# ioshield.net
KiCad netlist of a schematic drawn in EAGLE
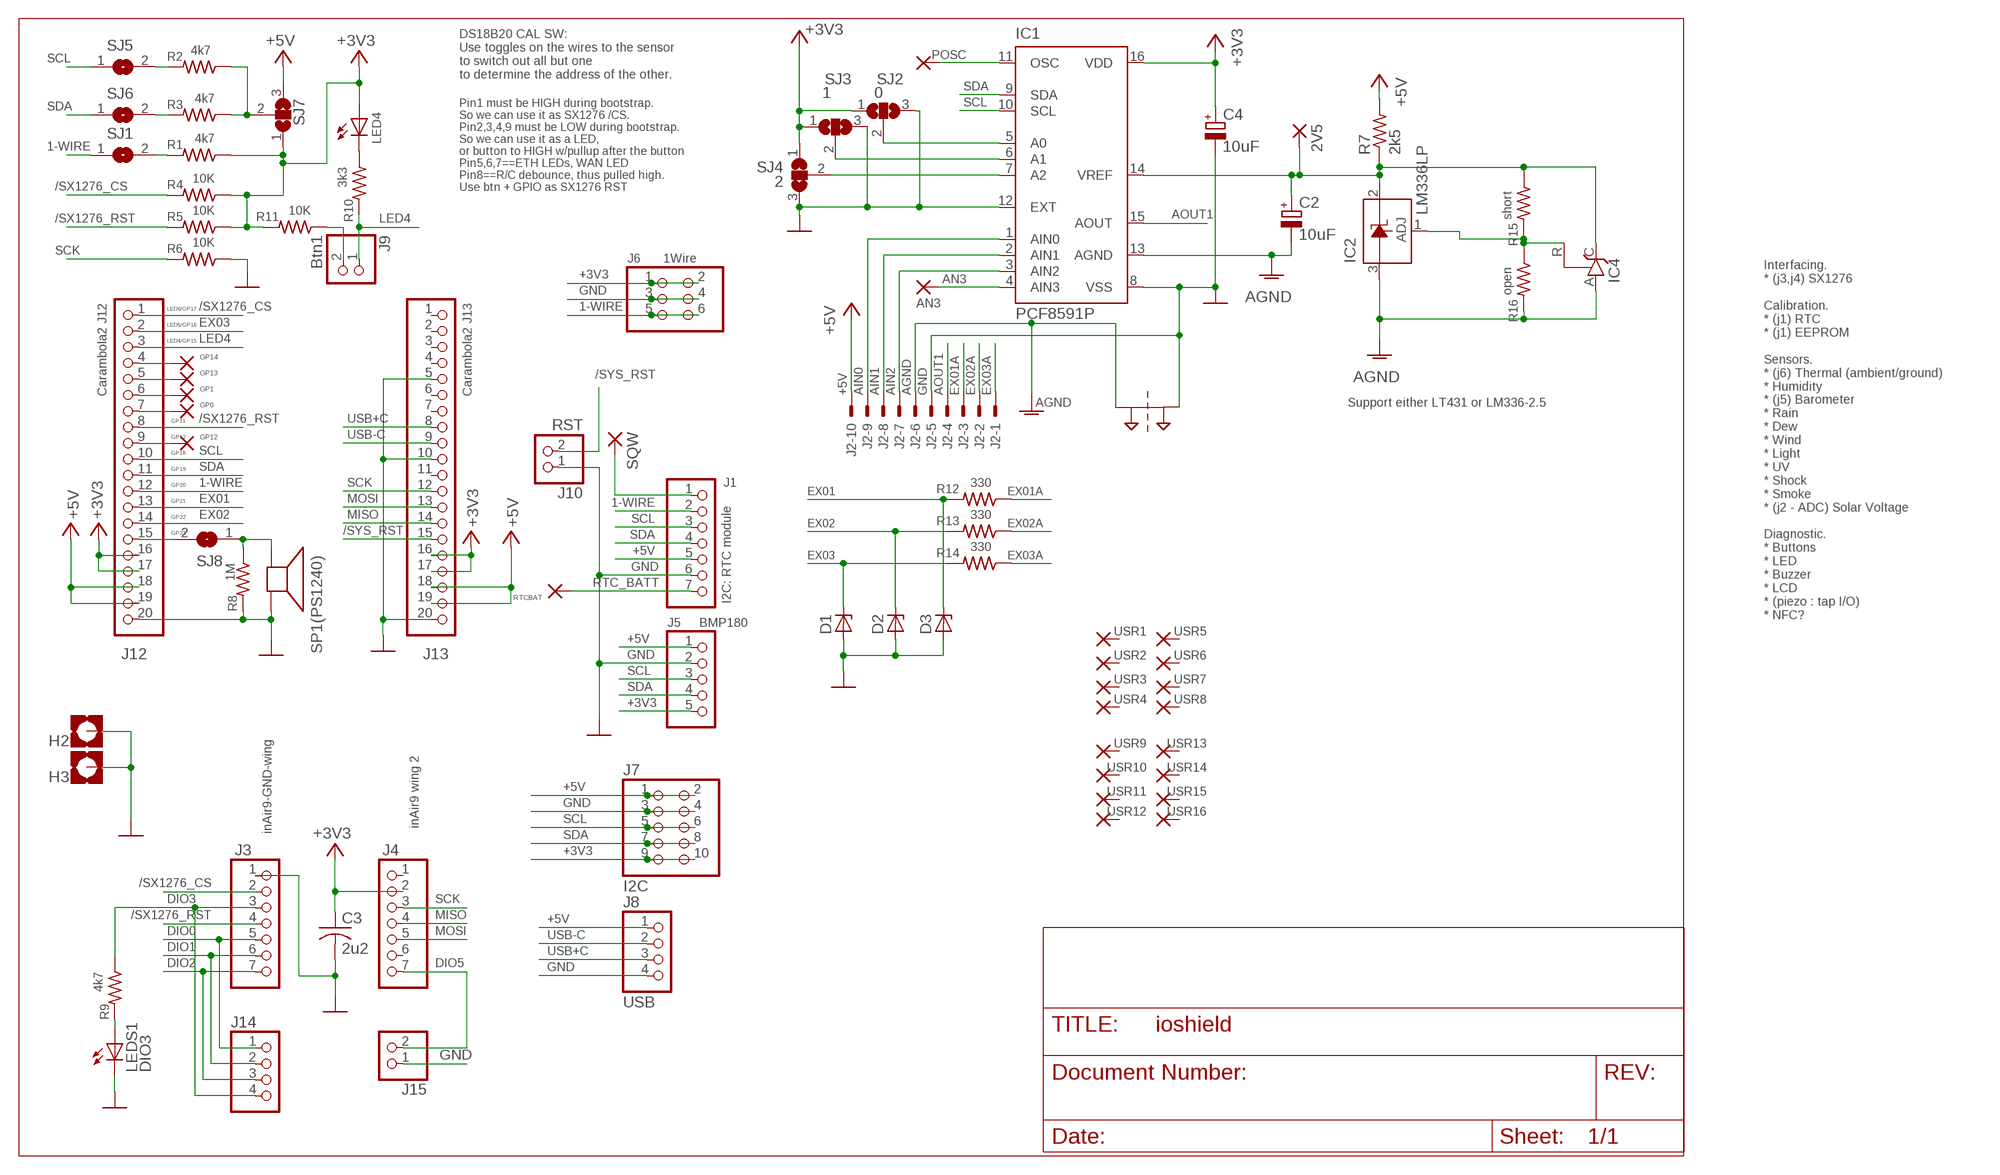
[diagram p0: schematic, sheet 1]

(export (version "E")
  (design (tool "Eeschema 10.0.6"))
  (components
    (comp (ref "2V5")
      (value "2,54/0,8")
      (footprint "eagle-import:2,54_0,8")
      (libsource (lib "eagle-import") (part "2,54/0,8"))
    )
    (comp (ref "AN3")
      (value "AN3")
      (footprint "eagle-import:2,54_0,8")
      (libsource (lib "eagle-import") (part "2,54/0,8"))
    )
    (comp (ref "C2")
      (value "10uF")
      (footprint "eagle-import:E2,5-5")
      (libsource (lib "eagle-import") (part "CPOL-EUE2.5-5"))
    )
    (comp (ref "C3")
      (value "2u2")
      (footprint "eagle-import:C1206")
      (libsource (lib "eagle-import") (part "C-USC1206"))
    )
    (comp (ref "C4")
      (value "10uF")
      (footprint "eagle-import:E2,5-5")
      (libsource (lib "eagle-import") (part "CPOL-EUE2.5-5"))
    )
    (comp (ref "D1")
      (value "ZENER-DIODEZD-2.5")
      (footprint "eagle-import:ZDIO-2.5")
      (libsource (lib "eagle-import") (part "ZENER-DIODEZD-2.5"))
    )
    (comp (ref "D2")
      (value "ZENER-DIODEZD-2.5")
      (footprint "eagle-import:ZDIO-2.5")
      (libsource (lib "eagle-import") (part "ZENER-DIODEZD-2.5"))
    )
    (comp (ref "D3")
      (value "ZENER-DIODEZD-2.5")
      (footprint "eagle-import:ZDIO-2.5")
      (libsource (lib "eagle-import") (part "ZENER-DIODEZD-2.5"))
    )
    (comp (ref "GP0")
      (value "2,54/0,8")
      (footprint "eagle-import:2,54_0,8")
      (libsource (lib "eagle-import") (part "2,54/0,8"))
    )
    (comp (ref "GP1")
      (value "2,54/0,8")
      (footprint "eagle-import:2,54_0,8")
      (libsource (lib "eagle-import") (part "2,54/0,8"))
    )
    (comp (ref "GP12")
      (value "2,54/0,8")
      (footprint "eagle-import:2,54_0,8")
      (libsource (lib "eagle-import") (part "2,54/0,8"))
    )
    (comp (ref "GP13")
      (value "2,54/0,8")
      (footprint "eagle-import:2,54_0,8")
      (libsource (lib "eagle-import") (part "2,54/0,8"))
    )
    (comp (ref "GP14")
      (value "2,54/0,8")
      (footprint "eagle-import:2,54_0,8")
      (libsource (lib "eagle-import") (part "2,54/0,8"))
    )
    (comp (ref "H2")
      (value "MOUNT-PAD-SQUARE3.2")
      (footprint "eagle-import:3,2-PAD-SQUARE")
      (libsource (lib "eagle-import") (part "MOUNT-PAD-SQUARE3.2"))
    )
    (comp (ref "H3")
      (value "MOUNT-PAD-SQUARE3.2")
      (footprint "eagle-import:3,2-PAD-SQUARE")
      (libsource (lib "eagle-import") (part "MOUNT-PAD-SQUARE3.2"))
    )
    (comp (ref "IC1")
      (value "PCF8591P")
      (footprint "eagle-import:DIL16")
      (fields (field (name "MF") "FARNELL"))
      (libsource (lib "eagle-import") (part "PCF8591P"))
    )
    (comp (ref "IC2")
      (value "LM336LP")
      (footprint "eagle-import:TO92")
      (libsource (lib "eagle-import") (part "LM336LP"))
    )
    (comp (ref "IC4")
      (value "TL431CLP")
      (footprint "eagle-import:TO92-CLP")
      (libsource (lib "eagle-import") (part "TL431CLP"))
    )
    (comp (ref "J1")
      (value "I2C: RTC module")
      (footprint "eagle-import:1X07")
      (libsource (lib "eagle-import") (part "PINHD-1X7"))
    )
    (comp (ref "J2")
      (value "22-23-2101")
      (footprint "eagle-import:22-23-2101")
      (fields (field (name "MF") "MOLEX") (field (name "MPN") "Screw Terminal"))
      (libsource (lib "eagle-import") (part "22-23-2101"))
    )
    (comp (ref "J3")
      (value "inAir9-GND-wing")
      (footprint "eagle-import:1X07")
      (libsource (lib "eagle-import") (part "PINHD-1X7"))
    )
    (comp (ref "J4")
      (value "inAir9 wing 2")
      (footprint "eagle-import:1X07")
      (libsource (lib "eagle-import") (part "PINHD-1X7"))
    )
    (comp (ref "J5")
      (value "BMP180")
      (footprint "eagle-import:1X05")
      (libsource (lib "eagle-import") (part "PINHD-1X5"))
    )
    (comp (ref "J6")
      (value "1Wire")
      (footprint "eagle-import:2X03")
      (libsource (lib "eagle-import") (part "PINHD-2X3"))
    )
    (comp (ref "J7")
      (value "I2C")
      (footprint "eagle-import:2X05")
      (libsource (lib "eagle-import") (part "PINHD-2X5"))
    )
    (comp (ref "J8")
      (value "USB")
      (footprint "eagle-import:1X04")
      (libsource (lib "eagle-import") (part "PINHD-1X4"))
    )
    (comp (ref "J9")
      (value "Btn1")
      (footprint "eagle-import:1X02")
      (libsource (lib "eagle-import") (part "PINHD-1X2"))
    )
    (comp (ref "J10")
      (value "RST")
      (footprint "eagle-import:1X02")
      (libsource (lib "eagle-import") (part "PINHD-1X2"))
    )
    (comp (ref "J12")
      (value "Carambola2 J12")
      (footprint "eagle-import:1X20")
      (libsource (lib "eagle-import") (part "PINHD-1X20"))
    )
    (comp (ref "J13")
      (value "Carambola2 J13")
      (footprint "eagle-import:1X20")
      (libsource (lib "eagle-import") (part "PINHD-1X20"))
    )
    (comp (ref "J14")
      (value "PINHD-1X4")
      (footprint "eagle-import:1X04")
      (libsource (lib "eagle-import") (part "PINHD-1X4"))
    )
    (comp (ref "J15")
      (value "PINHD-1X2")
      (footprint "eagle-import:1X02")
      (libsource (lib "eagle-import") (part "PINHD-1X2"))
    )
    (comp (ref "LED4")
      (value "LED3MM")
      (footprint "eagle-import:LED3MM")
      (libsource (lib "eagle-import") (part "LED3MM"))
    )
    (comp (ref "LEDS1")
      (value "DIO3")
      (footprint "eagle-import:LED3MM")
      (libsource (lib "eagle-import") (part "LED3MM"))
    )
    (comp (ref "POSC")
      (value "2,54/0,8")
      (footprint "eagle-import:2,54_0,8")
      (libsource (lib "eagle-import") (part "2,54/0,8"))
    )
    (comp (ref "PT1")
      (value "2PT_GND_TIE")
      (footprint "eagle-import:2PT_GND_TIE")
      (libsource (lib "eagle-import") (part "2PT_GND_TIE"))
    )
    (comp (ref "R1")
      (value "4k7")
      (footprint "eagle-import:M1206")
      (libsource (lib "eagle-import") (part "R-US_M1206"))
    )
    (comp (ref "R2")
      (value "4k7")
      (footprint "eagle-import:M1206")
      (libsource (lib "eagle-import") (part "R-US_M1206"))
    )
    (comp (ref "R3")
      (value "4k7")
      (footprint "eagle-import:M1206")
      (libsource (lib "eagle-import") (part "R-US_M1206"))
    )
    (comp (ref "R4")
      (value "10K")
      (footprint "eagle-import:M1206")
      (libsource (lib "eagle-import") (part "R-US_M1206"))
    )
    (comp (ref "R5")
      (value "10K")
      (footprint "eagle-import:M1206")
      (libsource (lib "eagle-import") (part "R-US_M1206"))
    )
    (comp (ref "R6")
      (value "10K")
      (footprint "eagle-import:M1206")
      (libsource (lib "eagle-import") (part "R-US_M1206"))
    )
    (comp (ref "R7")
      (value "2k5")
      (footprint "eagle-import:M1206")
      (libsource (lib "eagle-import") (part "R-US_M1206"))
    )
    (comp (ref "R8")
      (value "1M")
      (footprint "eagle-import:M1206")
      (libsource (lib "eagle-import") (part "R-US_M1206"))
    )
    (comp (ref "R9")
      (value "4k7")
      (footprint "eagle-import:M1206")
      (libsource (lib "eagle-import") (part "R-US_M1206"))
    )
    (comp (ref "R10")
      (value "3k3")
      (footprint "eagle-import:M1206")
      (libsource (lib "eagle-import") (part "R-US_M1206"))
    )
    (comp (ref "R11")
      (value "10K")
      (footprint "eagle-import:M1206")
      (libsource (lib "eagle-import") (part "R-US_M1206"))
    )
    (comp (ref "R12")
      (value "330")
      (footprint "eagle-import:M1206")
      (libsource (lib "eagle-import") (part "R-US_M1206"))
    )
    (comp (ref "R13")
      (value "330")
      (footprint "eagle-import:M1206")
      (libsource (lib "eagle-import") (part "R-US_M1206"))
    )
    (comp (ref "R14")
      (value "330")
      (footprint "eagle-import:M1206")
      (libsource (lib "eagle-import") (part "R-US_M1206"))
    )
    (comp (ref "R15")
      (value "short")
      (footprint "eagle-import:M1206")
      (libsource (lib "eagle-import") (part "R-US_M1206"))
    )
    (comp (ref "R16")
      (value "open")
      (footprint "eagle-import:M1206")
      (libsource (lib "eagle-import") (part "R-US_M1206"))
    )
    (comp (ref "RTCBAT")
      (value "2,54/0,8")
      (footprint "eagle-import:2,54_0,8")
      (libsource (lib "eagle-import") (part "2,54/0,8"))
    )
    (comp (ref "SJ1") (value "SJ") (footprint "eagle-import:SJ") (libsource (lib "eagle-import") (part "SJ")))
    (comp (ref "SJ2")
      (value "0")
      (footprint "eagle-import:SJ_2")
      (libsource (lib "eagle-import") (part "SJ2W"))
    )
    (comp (ref "SJ3")
      (value "1")
      (footprint "eagle-import:SJ_2")
      (libsource (lib "eagle-import") (part "SJ2W"))
    )
    (comp (ref "SJ4")
      (value "2")
      (footprint "eagle-import:SJ_2")
      (libsource (lib "eagle-import") (part "SJ2W"))
    )
    (comp (ref "SJ5") (value "SJ") (footprint "eagle-import:SJ") (libsource (lib "eagle-import") (part "SJ")))
    (comp (ref "SJ6") (value "SJ") (footprint "eagle-import:SJ") (libsource (lib "eagle-import") (part "SJ")))
    (comp (ref "SJ7")
      (value "SJ2W")
      (footprint "eagle-import:SJ_2")
      (libsource (lib "eagle-import") (part "SJ2W"))
    )
    (comp (ref "SJ8") (value "SJ") (footprint "eagle-import:SJ") (libsource (lib "eagle-import") (part "SJ")))
    (comp (ref "SP1(PS1240)")
      (value "SPEAKER/AL11P")
      (footprint "eagle-import:AL11P")
      (libsource (lib "eagle-import") (part "SPEAKER/AL11P"))
    )
    (comp (ref "SQW")
      (value "2,54/0,8")
      (footprint "eagle-import:2,54_0,8")
      (libsource (lib "eagle-import") (part "2,54/0,8"))
    )
    (comp (ref "USR1")
      (value "1,6/0,8")
      (footprint "eagle-import:1,6_0,8")
      (libsource (lib "eagle-import") (part "1,6/0,8"))
    )
    (comp (ref "USR2")
      (value "1,6/0,8")
      (footprint "eagle-import:1,6_0,8")
      (libsource (lib "eagle-import") (part "1,6/0,8"))
    )
    (comp (ref "USR3")
      (value "1,6/0,8")
      (footprint "eagle-import:1,6_0,8")
      (libsource (lib "eagle-import") (part "1,6/0,8"))
    )
    (comp (ref "USR4")
      (value "1,6/0,8")
      (footprint "eagle-import:1,6_0,8")
      (libsource (lib "eagle-import") (part "1,6/0,8"))
    )
    (comp (ref "USR5")
      (value "1,6/0,8")
      (footprint "eagle-import:1,6_0,8")
      (libsource (lib "eagle-import") (part "1,6/0,8"))
    )
    (comp (ref "USR6")
      (value "1,6/0,8")
      (footprint "eagle-import:1,6_0,8")
      (libsource (lib "eagle-import") (part "1,6/0,8"))
    )
    (comp (ref "USR7")
      (value "1,6/0,8")
      (footprint "eagle-import:1,6_0,8")
      (libsource (lib "eagle-import") (part "1,6/0,8"))
    )
    (comp (ref "USR8")
      (value "1,6/0,8")
      (footprint "eagle-import:1,6_0,8")
      (libsource (lib "eagle-import") (part "1,6/0,8"))
    )
    (comp (ref "USR9")
      (value "1,6/0,8")
      (footprint "eagle-import:1,6_0,8")
      (libsource (lib "eagle-import") (part "1,6/0,8"))
    )
    (comp (ref "USR10")
      (value "1,6/0,8")
      (footprint "eagle-import:1,6_0,8")
      (libsource (lib "eagle-import") (part "1,6/0,8"))
    )
    (comp (ref "USR11")
      (value "1,6/0,8")
      (footprint "eagle-import:1,6_0,8")
      (libsource (lib "eagle-import") (part "1,6/0,8"))
    )
    (comp (ref "USR12")
      (value "1,6/0,8")
      (footprint "eagle-import:1,6_0,8")
      (libsource (lib "eagle-import") (part "1,6/0,8"))
    )
    (comp (ref "USR13")
      (value "1,6/0,8")
      (footprint "eagle-import:1,6_0,8")
      (libsource (lib "eagle-import") (part "1,6/0,8"))
    )
    (comp (ref "USR14")
      (value "1,6/0,8")
      (footprint "eagle-import:1,6_0,8")
      (libsource (lib "eagle-import") (part "1,6/0,8"))
    )
    (comp (ref "USR15")
      (value "1,6/0,8")
      (footprint "eagle-import:1,6_0,8")
      (libsource (lib "eagle-import") (part "1,6/0,8"))
    )
    (comp (ref "USR16")
      (value "1,6/0,8")
      (footprint "eagle-import:1,6_0,8")
      (libsource (lib "eagle-import") (part "1,6/0,8"))
    )
  )
  (nets
    (net (code "1") (name "+3V3") (class "Default")
      (node (ref "C3") (pin "1") (pinfunction "1_1") (pintype "passive"))
      (node (ref "C4") (pin "+") (pinfunction "+_+") (pintype "passive"))
      (node (ref "IC1") (pin "16") (pinfunction "VDD_16") (pintype "power_in"))
      (node (ref "J12") (pin "16") (pinfunction "16_16") (pintype "passive"))
      (node (ref "J12") (pin "17") (pinfunction "17_17") (pintype "passive"))
      (node (ref "J13") (pin "16") (pinfunction "16_16") (pintype "passive"))
      (node (ref "J13") (pin "17") (pinfunction "17_17") (pintype "passive"))
      (node (ref "J4") (pin "2") (pinfunction "2_2") (pintype "passive"))
      (node (ref "J5") (pin "5") (pinfunction "5_5") (pintype "passive"))
      (node (ref "J6") (pin "1") (pinfunction "1_1") (pintype "passive"))
      (node (ref "J6") (pin "2") (pinfunction "2_2") (pintype "passive"))
      (node (ref "J7") (pin "10") (pinfunction "10_10") (pintype "passive"))
      (node (ref "J7") (pin "9") (pinfunction "9_9") (pintype "passive"))
      (node (ref "LED4") (pin "A") (pinfunction "A_A") (pintype "passive"))
      (node (ref "R1") (pin "1") (pinfunction "1_1") (pintype "passive"))
      (node (ref "R11") (pin "2") (pinfunction "2_2") (pintype "passive"))
      (node (ref "R4") (pin "1") (pinfunction "1_1") (pintype "passive"))
      (node (ref "R5") (pin "1") (pinfunction "1_1") (pintype "passive"))
      (node (ref "SJ2") (pin "1") (pinfunction "1_1") (pintype "passive"))
      (node (ref "SJ3") (pin "1") (pinfunction "1_1") (pintype "passive"))
      (node (ref "SJ4") (pin "1") (pinfunction "1_1") (pintype "passive"))
      (node (ref "SJ7") (pin "1") (pinfunction "1_1") (pintype "passive"))
    )
    (net (code "2") (name "+5V") (class "Default")
      (node (ref "J1") (pin "5") (pinfunction "5_5") (pintype "passive"))
      (node (ref "J12") (pin "18") (pinfunction "18_18") (pintype "passive"))
      (node (ref "J12") (pin "19") (pinfunction "19_19") (pintype "passive"))
      (node (ref "J13") (pin "18") (pinfunction "18_18") (pintype "passive"))
      (node (ref "J13") (pin "19") (pinfunction "19_19") (pintype "passive"))
      (node (ref "J2") (pin "10") (pinfunction "S_10") (pintype "passive"))
      (node (ref "J5") (pin "1") (pinfunction "1_1") (pintype "passive"))
      (node (ref "J7") (pin "1") (pinfunction "1_1") (pintype "passive"))
      (node (ref "J7") (pin "2") (pinfunction "2_2") (pintype "passive"))
      (node (ref "J8") (pin "1") (pinfunction "1_1") (pintype "passive"))
      (node (ref "R7") (pin "2") (pinfunction "2_2") (pintype "passive"))
      (node (ref "SJ7") (pin "3") (pinfunction "3_3") (pintype "passive"))
    )
    (net (code "3") (name "/1-WIRE") (class "Default")
      (node (ref "J1") (pin "2") (pinfunction "2_2") (pintype "passive"))
      (node (ref "J12") (pin "12") (pinfunction "12_12") (pintype "passive"))
      (node (ref "J6") (pin "5") (pinfunction "5_5") (pintype "passive"))
      (node (ref "J6") (pin "6") (pinfunction "6_6") (pintype "passive"))
      (node (ref "SJ1") (pin "1") (pinfunction "1_1") (pintype "passive"))
    )
    (net (code "4") (name "/AIN0") (class "Default")
      (node (ref "IC1") (pin "1") (pinfunction "AIN0_1") (pintype "input"))
      (node (ref "J2") (pin "9") (pinfunction "S_9") (pintype "passive"))
    )
    (net (code "5") (name "/AIN1") (class "Default")
      (node (ref "IC1") (pin "2") (pinfunction "AIN1_2") (pintype "input"))
      (node (ref "J2") (pin "8") (pinfunction "S_8") (pintype "passive"))
    )
    (net (code "6") (name "/AIN2") (class "Default")
      (node (ref "IC1") (pin "3") (pinfunction "AIN2_3") (pintype "input"))
      (node (ref "J2") (pin "7") (pinfunction "S_7") (pintype "passive"))
    )
    (net (code "7") (name "/AOUT1") (class "Default")
      (node (ref "IC1") (pin "15") (pinfunction "AOUT_15") (pintype "output"))
      (node (ref "J2") (pin "4") (pinfunction "S_4") (pintype "passive"))
    )
    (net (code "8") (name "/DIO0") (class "Default")
      (node (ref "J14") (pin "1") (pinfunction "1_1") (pintype "passive"))
      (node (ref "J3") (pin "5") (pinfunction "5_5") (pintype "passive"))
    )
    (net (code "9") (name "/DIO1") (class "Default")
      (node (ref "J14") (pin "2") (pinfunction "2_2") (pintype "passive"))
      (node (ref "J3") (pin "6") (pinfunction "6_6") (pintype "passive"))
    )
    (net (code "10") (name "/DIO2") (class "Default")
      (node (ref "J14") (pin "3") (pinfunction "3_3") (pintype "passive"))
      (node (ref "J3") (pin "7") (pinfunction "7_7") (pintype "passive"))
    )
    (net (code "11") (name "/DIO3") (class "Default")
      (node (ref "J14") (pin "4") (pinfunction "4_4") (pintype "passive"))
      (node (ref "J3") (pin "3") (pinfunction "3_3") (pintype "passive"))
      (node (ref "R9") (pin "1") (pinfunction "1_1") (pintype "passive"))
    )
    (net (code "12") (name "/DIO5") (class "Default")
      (node (ref "J15") (pin "2") (pinfunction "2_2") (pintype "passive"))
      (node (ref "J4") (pin "7") (pinfunction "7_7") (pintype "passive"))
    )
    (net (code "13") (name "/EX01") (class "Default")
      (node (ref "D3") (pin "C") (pinfunction "C_C") (pintype "passive"))
      (node (ref "J12") (pin "13") (pinfunction "13_13") (pintype "passive"))
      (node (ref "R12") (pin "2") (pinfunction "2_2") (pintype "passive"))
    )
    (net (code "14") (name "/EX01A") (class "Default")
      (node (ref "J2") (pin "3") (pinfunction "S_3") (pintype "passive"))
      (node (ref "R12") (pin "1") (pinfunction "1_1") (pintype "passive"))
    )
    (net (code "15") (name "/EX02") (class "Default")
      (node (ref "D2") (pin "C") (pinfunction "C_C") (pintype "passive"))
      (node (ref "J12") (pin "14") (pinfunction "14_14") (pintype "passive"))
      (node (ref "R13") (pin "2") (pinfunction "2_2") (pintype "passive"))
    )
    (net (code "16") (name "/EX02A") (class "Default")
      (node (ref "J2") (pin "2") (pinfunction "S_2") (pintype "passive"))
      (node (ref "R13") (pin "1") (pinfunction "1_1") (pintype "passive"))
    )
    (net (code "17") (name "/EX03") (class "Default")
      (node (ref "D1") (pin "C") (pinfunction "C_C") (pintype "passive"))
      (node (ref "J12") (pin "2") (pinfunction "2_2") (pintype "passive"))
      (node (ref "R14") (pin "2") (pinfunction "2_2") (pintype "passive"))
    )
    (net (code "18") (name "/EX03A") (class "Default")
      (node (ref "J2") (pin "1") (pinfunction "S_1") (pintype "passive"))
      (node (ref "R14") (pin "1") (pinfunction "1_1") (pintype "passive"))
    )
    (net (code "19") (name "/LED4") (class "Default")
      (node (ref "J12") (pin "3") (pinfunction "3_3") (pintype "passive"))
      (node (ref "J9") (pin "1") (pinfunction "1_1") (pintype "passive"))
      (node (ref "R10") (pin "2") (pinfunction "2_2") (pintype "passive"))
    )
    (net (code "20") (name "/MISO") (class "Default")
      (node (ref "J13") (pin "14") (pinfunction "14_14") (pintype "passive"))
      (node (ref "J4") (pin "4") (pinfunction "4_4") (pintype "passive"))
    )
    (net (code "21") (name "/MOSI") (class "Default")
      (node (ref "J13") (pin "13") (pinfunction "13_13") (pintype "passive"))
      (node (ref "J4") (pin "5") (pinfunction "5_5") (pintype "passive"))
    )
    (net (code "22") (name "/RTC_BATT") (class "Default")
      (node (ref "J1") (pin "7") (pinfunction "7_7") (pintype "passive"))
      (node (ref "RTCBAT") (pin "1") (pinfunction "P_1") (pintype "passive"))
    )
    (net (code "23") (name "/SCK") (class "Default")
      (node (ref "J13") (pin "12") (pinfunction "12_12") (pintype "passive"))
      (node (ref "J4") (pin "3") (pinfunction "3_3") (pintype "passive"))
      (node (ref "R6") (pin "2") (pinfunction "2_2") (pintype "passive"))
    )
    (net (code "24") (name "/SCL") (class "Default")
      (node (ref "IC1") (pin "10") (pinfunction "SCL_10") (pintype "input"))
      (node (ref "J1") (pin "3") (pinfunction "3_3") (pintype "passive"))
      (node (ref "J12") (pin "10") (pinfunction "10_10") (pintype "passive"))
      (node (ref "J5") (pin "3") (pinfunction "3_3") (pintype "passive"))
      (node (ref "J7") (pin "5") (pinfunction "5_5") (pintype "passive"))
      (node (ref "J7") (pin "6") (pinfunction "6_6") (pintype "passive"))
      (node (ref "SJ5") (pin "1") (pinfunction "1_1") (pintype "passive"))
    )
    (net (code "25") (name "/SDA") (class "Default")
      (node (ref "IC1") (pin "9") (pinfunction "SDA_9") (pintype "bidirectional"))
      (node (ref "J1") (pin "4") (pinfunction "4_4") (pintype "passive"))
      (node (ref "J12") (pin "11") (pinfunction "11_11") (pintype "passive"))
      (node (ref "J5") (pin "4") (pinfunction "4_4") (pintype "passive"))
      (node (ref "J7") (pin "7") (pinfunction "7_7") (pintype "passive"))
      (node (ref "J7") (pin "8") (pinfunction "8_8") (pintype "passive"))
      (node (ref "SJ6") (pin "1") (pinfunction "1_1") (pintype "passive"))
    )
    (net (code "26") (name "/USB+C") (class "Default")
      (node (ref "J13") (pin "8") (pinfunction "8_8") (pintype "passive"))
      (node (ref "J8") (pin "3") (pinfunction "3_3") (pintype "passive"))
    )
    (net (code "27") (name "/USB-C") (class "Default")
      (node (ref "J13") (pin "9") (pinfunction "9_9") (pintype "passive"))
      (node (ref "J8") (pin "2") (pinfunction "2_2") (pintype "passive"))
    )
    (net (code "28") (name "/{slash}SX1276_CS") (class "Default")
      (node (ref "J12") (pin "1") (pinfunction "1_1") (pintype "passive"))
      (node (ref "J3") (pin "2") (pinfunction "2_2") (pintype "passive"))
      (node (ref "R4") (pin "2") (pinfunction "2_2") (pintype "passive"))
    )
    (net (code "29") (name "/{slash}SX1276_RST") (class "Default")
      (node (ref "J12") (pin "8") (pinfunction "8_8") (pintype "passive"))
      (node (ref "J3") (pin "4") (pinfunction "4_4") (pintype "passive"))
      (node (ref "R5") (pin "2") (pinfunction "2_2") (pintype "passive"))
    )
    (net (code "30") (name "/{slash}SYS_RST") (class "Default")
      (node (ref "J10") (pin "2") (pinfunction "2_2") (pintype "passive"))
      (node (ref "J13") (pin "15") (pinfunction "15_15") (pintype "passive"))
    )
    (net (code "31") (name "AGND") (class "Default")
      (node (ref "C2") (pin "-") (pinfunction "-_-") (pintype "passive"))
      (node (ref "IC1") (pin "13") (pinfunction "AGND_13") (pintype "power_in"))
      (node (ref "IC2") (pin "3") (pinfunction "A_3") (pintype "input"))
      (node (ref "IC4") (pin "A") (pinfunction "A_A") (pintype "passive"))
      (node (ref "J2") (pin "6") (pinfunction "S_6") (pintype "passive"))
      (node (ref "PT1") (pin "P$1") (pinfunction "P$1_P$1") (pintype "bidirectional"))
      (node (ref "R16") (pin "2") (pinfunction "2_2") (pintype "passive"))
    )
    (net (code "32") (name "GND") (class "Default")
      (node (ref "C3") (pin "2") (pinfunction "2_2") (pintype "passive"))
      (node (ref "C4") (pin "-") (pinfunction "-_-") (pintype "passive"))
      (node (ref "D1") (pin "A") (pinfunction "A_A") (pintype "passive"))
      (node (ref "D2") (pin "A") (pinfunction "A_A") (pintype "passive"))
      (node (ref "D3") (pin "A") (pinfunction "A_A") (pintype "passive"))
      (node (ref "H2") (pin "B3,2") (pinfunction "MOUNT_B3,2") (pintype "passive"))
      (node (ref "H3") (pin "B3,2") (pinfunction "MOUNT_B3,2") (pintype "passive"))
      (node (ref "IC1") (pin "12") (pinfunction "EXT_12") (pintype "input"))
      (node (ref "IC1") (pin "8") (pinfunction "VSS_8") (pintype "power_in"))
      (node (ref "J1") (pin "6") (pinfunction "6_6") (pintype "passive"))
      (node (ref "J10") (pin "1") (pinfunction "1_1") (pintype "passive"))
      (node (ref "J12") (pin "20") (pinfunction "20_20") (pintype "passive"))
      (node (ref "J13") (pin "10") (pinfunction "10_10") (pintype "passive"))
      (node (ref "J13") (pin "20") (pinfunction "20_20") (pintype "passive"))
      (node (ref "J13") (pin "5") (pinfunction "5_5") (pintype "passive"))
      (node (ref "J15") (pin "1") (pinfunction "1_1") (pintype "passive"))
      (node (ref "J2") (pin "5") (pinfunction "S_5") (pintype "passive"))
      (node (ref "J3") (pin "1") (pinfunction "1_1") (pintype "passive"))
      (node (ref "J5") (pin "2") (pinfunction "2_2") (pintype "passive"))
      (node (ref "J6") (pin "3") (pinfunction "3_3") (pintype "passive"))
      (node (ref "J6") (pin "4") (pinfunction "4_4") (pintype "passive"))
      (node (ref "J7") (pin "3") (pinfunction "3_3") (pintype "passive"))
      (node (ref "J7") (pin "4") (pinfunction "4_4") (pintype "passive"))
      (node (ref "J8") (pin "4") (pinfunction "4_4") (pintype "passive"))
      (node (ref "LEDS1") (pin "K") (pinfunction "C_K") (pintype "passive"))
      (node (ref "PT1") (pin "P$2") (pinfunction "P$2_P$2") (pintype "bidirectional"))
      (node (ref "R6") (pin "1") (pinfunction "1_1") (pintype "passive"))
      (node (ref "R8") (pin "2") (pinfunction "2_2") (pintype "passive"))
      (node (ref "SJ2") (pin "3") (pinfunction "3_3") (pintype "passive"))
      (node (ref "SJ3") (pin "3") (pinfunction "3_3") (pintype "passive"))
      (node (ref "SJ4") (pin "3") (pinfunction "3_3") (pintype "passive"))
      (node (ref "SP1(PS1240)") (pin "-") (pinfunction "-_-") (pintype "passive"))
    )
    (net (code "33") (name "Net-(2V5-P)") (class "Default")
      (node (ref "2V5") (pin "1") (pinfunction "P_1") (pintype "passive"))
      (node (ref "C2") (pin "+") (pinfunction "+_+") (pintype "passive"))
      (node (ref "IC1") (pin "14") (pinfunction "VREF_14") (pintype "input"))
      (node (ref "IC2") (pin "2") (pinfunction "C_2") (pintype "passive"))
      (node (ref "IC4") (pin "C") (pinfunction "C_C") (pintype "passive"))
      (node (ref "R15") (pin "1") (pinfunction "1_1") (pintype "passive"))
      (node (ref "R7") (pin "1") (pinfunction "1_1") (pintype "passive"))
    )
    (net (code "34") (name "Net-(AN3-P)") (class "Default")
      (node (ref "AN3") (pin "1") (pinfunction "P_1") (pintype "passive"))
      (node (ref "IC1") (pin "4") (pinfunction "AIN3_4") (pintype "input"))
    )
    (net (code "35") (name "Net-(GP0-P)") (class "Default")
      (node (ref "GP0") (pin "1") (pinfunction "P_1") (pintype "passive"))
      (node (ref "J12") (pin "7") (pinfunction "7_7") (pintype "passive"))
    )
    (net (code "36") (name "Net-(GP1-P)") (class "Default")
      (node (ref "GP1") (pin "1") (pinfunction "P_1") (pintype "passive"))
      (node (ref "J12") (pin "6") (pinfunction "6_6") (pintype "passive"))
    )
    (net (code "37") (name "Net-(GP12-P)") (class "Default")
      (node (ref "GP12") (pin "1") (pinfunction "P_1") (pintype "passive"))
      (node (ref "J12") (pin "9") (pinfunction "9_9") (pintype "passive"))
    )
    (net (code "38") (name "Net-(GP13-P)") (class "Default")
      (node (ref "GP13") (pin "1") (pinfunction "P_1") (pintype "passive"))
      (node (ref "J12") (pin "5") (pinfunction "5_5") (pintype "passive"))
    )
    (net (code "39") (name "Net-(GP14-P)") (class "Default")
      (node (ref "GP14") (pin "1") (pinfunction "P_1") (pintype "passive"))
      (node (ref "J12") (pin "4") (pinfunction "4_4") (pintype "passive"))
    )
    (net (code "40") (name "Net-(IC1-A0)") (class "Default")
      (node (ref "IC1") (pin "5") (pinfunction "A0_5") (pintype "input"))
      (node (ref "SJ2") (pin "2") (pinfunction "2_2") (pintype "passive"))
    )
    (net (code "41") (name "Net-(IC1-A1)") (class "Default")
      (node (ref "IC1") (pin "6") (pinfunction "A1_6") (pintype "input"))
      (node (ref "SJ3") (pin "2") (pinfunction "2_2") (pintype "passive"))
    )
    (net (code "42") (name "Net-(IC1-A2)") (class "Default")
      (node (ref "IC1") (pin "7") (pinfunction "A2_7") (pintype "input"))
      (node (ref "SJ4") (pin "2") (pinfunction "2_2") (pintype "passive"))
    )
    (net (code "43") (name "Net-(IC1-OSC)") (class "Default")
      (node (ref "IC1") (pin "11") (pinfunction "OSC_11") (pintype "input"))
      (node (ref "POSC") (pin "1") (pinfunction "P_1") (pintype "passive"))
    )
    (net (code "44") (name "Net-(IC2-ADJ)") (class "Default")
      (node (ref "IC2") (pin "1") (pinfunction "ADJ_1") (pintype "input"))
      (node (ref "IC4") (pin "R") (pinfunction "R_R") (pintype "passive"))
      (node (ref "R15") (pin "2") (pinfunction "2_2") (pintype "passive"))
      (node (ref "R16") (pin "1") (pinfunction "1_1") (pintype "passive"))
    )
    (net (code "45") (name "Net-(J9-Pad2)") (class "Default")
      (node (ref "J9") (pin "2") (pinfunction "2_2") (pintype "passive"))
      (node (ref "R11") (pin "1") (pinfunction "1_1") (pintype "passive"))
    )
    (net (code "46") (name "Net-(J12-Pad15)") (class "Default")
      (node (ref "J12") (pin "15") (pinfunction "15_15") (pintype "passive"))
      (node (ref "SJ8") (pin "2") (pinfunction "2_2") (pintype "passive"))
    )
    (net (code "47") (name "Net-(LED4-C)") (class "Default")
      (node (ref "LED4") (pin "K") (pinfunction "C_K") (pintype "passive"))
      (node (ref "R10") (pin "1") (pinfunction "1_1") (pintype "passive"))
    )
    (net (code "48") (name "Net-(LEDS1-PadA)") (class "Default")
      (node (ref "LEDS1") (pin "A") (pinfunction "A_A") (pintype "passive"))
      (node (ref "R9") (pin "2") (pinfunction "2_2") (pintype "passive"))
    )
    (net (code "49") (name "Net-(R1-Pad2)") (class "Default")
      (node (ref "R1") (pin "2") (pinfunction "2_2") (pintype "passive"))
      (node (ref "SJ1") (pin "2") (pinfunction "2_2") (pintype "passive"))
    )
    (net (code "50") (name "Net-(R2-Pad1)") (class "Default")
      (node (ref "R2") (pin "1") (pinfunction "1_1") (pintype "passive"))
      (node (ref "R3") (pin "1") (pinfunction "1_1") (pintype "passive"))
      (node (ref "SJ7") (pin "2") (pinfunction "2_2") (pintype "passive"))
    )
    (net (code "51") (name "Net-(R2-Pad2)") (class "Default")
      (node (ref "R2") (pin "2") (pinfunction "2_2") (pintype "passive"))
      (node (ref "SJ5") (pin "2") (pinfunction "2_2") (pintype "passive"))
    )
    (net (code "52") (name "Net-(R3-Pad2)") (class "Default")
      (node (ref "R3") (pin "2") (pinfunction "2_2") (pintype "passive"))
      (node (ref "SJ6") (pin "2") (pinfunction "2_2") (pintype "passive"))
    )
    (net (code "53") (name "Net-(R8-Pad1)") (class "Default")
      (node (ref "R8") (pin "1") (pinfunction "1_1") (pintype "passive"))
      (node (ref "SJ8") (pin "1") (pinfunction "1_1") (pintype "passive"))
      (node (ref "SP1(PS1240)") (pin "+") (pinfunction "+_+") (pintype "passive"))
    )
    (net (code "54") (name "Net-(SQW-P)") (class "Default")
      (node (ref "J1") (pin "1") (pinfunction "1_1") (pintype "passive"))
      (node (ref "SQW") (pin "1") (pinfunction "P_1") (pintype "passive"))
    )
    (net (code "55") (name "unconnected-(J4-Pad1)") (class "Default")
      (node (ref "J4") (pin "1") (pinfunction "1_1") (pintype "passive"))
    )
    (net (code "56") (name "unconnected-(J4-Pad6)") (class "Default")
      (node (ref "J4") (pin "6") (pinfunction "6_6") (pintype "passive"))
    )
    (net (code "57") (name "unconnected-(J13-Pad1)") (class "Default")
      (node (ref "J13") (pin "1") (pinfunction "1_1") (pintype "passive"))
    )
    (net (code "58") (name "unconnected-(J13-Pad2)") (class "Default")
      (node (ref "J13") (pin "2") (pinfunction "2_2") (pintype "passive"))
    )
    (net (code "59") (name "unconnected-(J13-Pad3)") (class "Default")
      (node (ref "J13") (pin "3") (pinfunction "3_3") (pintype "passive"))
    )
    (net (code "60") (name "unconnected-(J13-Pad4)") (class "Default")
      (node (ref "J13") (pin "4") (pinfunction "4_4") (pintype "passive"))
    )
    (net (code "61") (name "unconnected-(J13-Pad6)") (class "Default")
      (node (ref "J13") (pin "6") (pinfunction "6_6") (pintype "passive"))
    )
    (net (code "62") (name "unconnected-(J13-Pad7)") (class "Default")
      (node (ref "J13") (pin "7") (pinfunction "7_7") (pintype "passive"))
    )
    (net (code "63") (name "unconnected-(J13-Pad11)") (class "Default")
      (node (ref "J13") (pin "11") (pinfunction "11_11") (pintype "passive"))
    )
    (net (code "64") (name "unconnected-(USR1-P-Pad1)") (class "Default")
      (node (ref "USR1") (pin "1") (pinfunction "P_1") (pintype "passive"))
    )
    (net (code "65") (name "unconnected-(USR2-P-Pad1)") (class "Default")
      (node (ref "USR2") (pin "1") (pinfunction "P_1") (pintype "passive"))
    )
    (net (code "66") (name "unconnected-(USR3-P-Pad1)") (class "Default")
      (node (ref "USR3") (pin "1") (pinfunction "P_1") (pintype "passive"))
    )
    (net (code "67") (name "unconnected-(USR4-P-Pad1)") (class "Default")
      (node (ref "USR4") (pin "1") (pinfunction "P_1") (pintype "passive"))
    )
    (net (code "68") (name "unconnected-(USR5-P-Pad1)") (class "Default")
      (node (ref "USR5") (pin "1") (pinfunction "P_1") (pintype "passive"))
    )
    (net (code "69") (name "unconnected-(USR6-P-Pad1)") (class "Default")
      (node (ref "USR6") (pin "1") (pinfunction "P_1") (pintype "passive"))
    )
    (net (code "70") (name "unconnected-(USR7-P-Pad1)") (class "Default")
      (node (ref "USR7") (pin "1") (pinfunction "P_1") (pintype "passive"))
    )
    (net (code "71") (name "unconnected-(USR8-P-Pad1)") (class "Default")
      (node (ref "USR8") (pin "1") (pinfunction "P_1") (pintype "passive"))
    )
    (net (code "72") (name "unconnected-(USR9-P-Pad1)") (class "Default")
      (node (ref "USR9") (pin "1") (pinfunction "P_1") (pintype "passive"))
    )
    (net (code "73") (name "unconnected-(USR10-P-Pad1)") (class "Default")
      (node (ref "USR10") (pin "1") (pinfunction "P_1") (pintype "passive"))
    )
    (net (code "74") (name "unconnected-(USR11-P-Pad1)") (class "Default")
      (node (ref "USR11") (pin "1") (pinfunction "P_1") (pintype "passive"))
    )
    (net (code "75") (name "unconnected-(USR12-P-Pad1)") (class "Default")
      (node (ref "USR12") (pin "1") (pinfunction "P_1") (pintype "passive"))
    )
    (net (code "76") (name "unconnected-(USR13-P-Pad1)") (class "Default")
      (node (ref "USR13") (pin "1") (pinfunction "P_1") (pintype "passive"))
    )
    (net (code "77") (name "unconnected-(USR14-P-Pad1)") (class "Default")
      (node (ref "USR14") (pin "1") (pinfunction "P_1") (pintype "passive"))
    )
    (net (code "78") (name "unconnected-(USR15-P-Pad1)") (class "Default")
      (node (ref "USR15") (pin "1") (pinfunction "P_1") (pintype "passive"))
    )
    (net (code "79") (name "unconnected-(USR16-P-Pad1)") (class "Default")
      (node (ref "USR16") (pin "1") (pinfunction "P_1") (pintype "passive"))
    )
  )
)
